# 01_POWER.net
KiCad netlist of a schematic drawn in Altium Designer
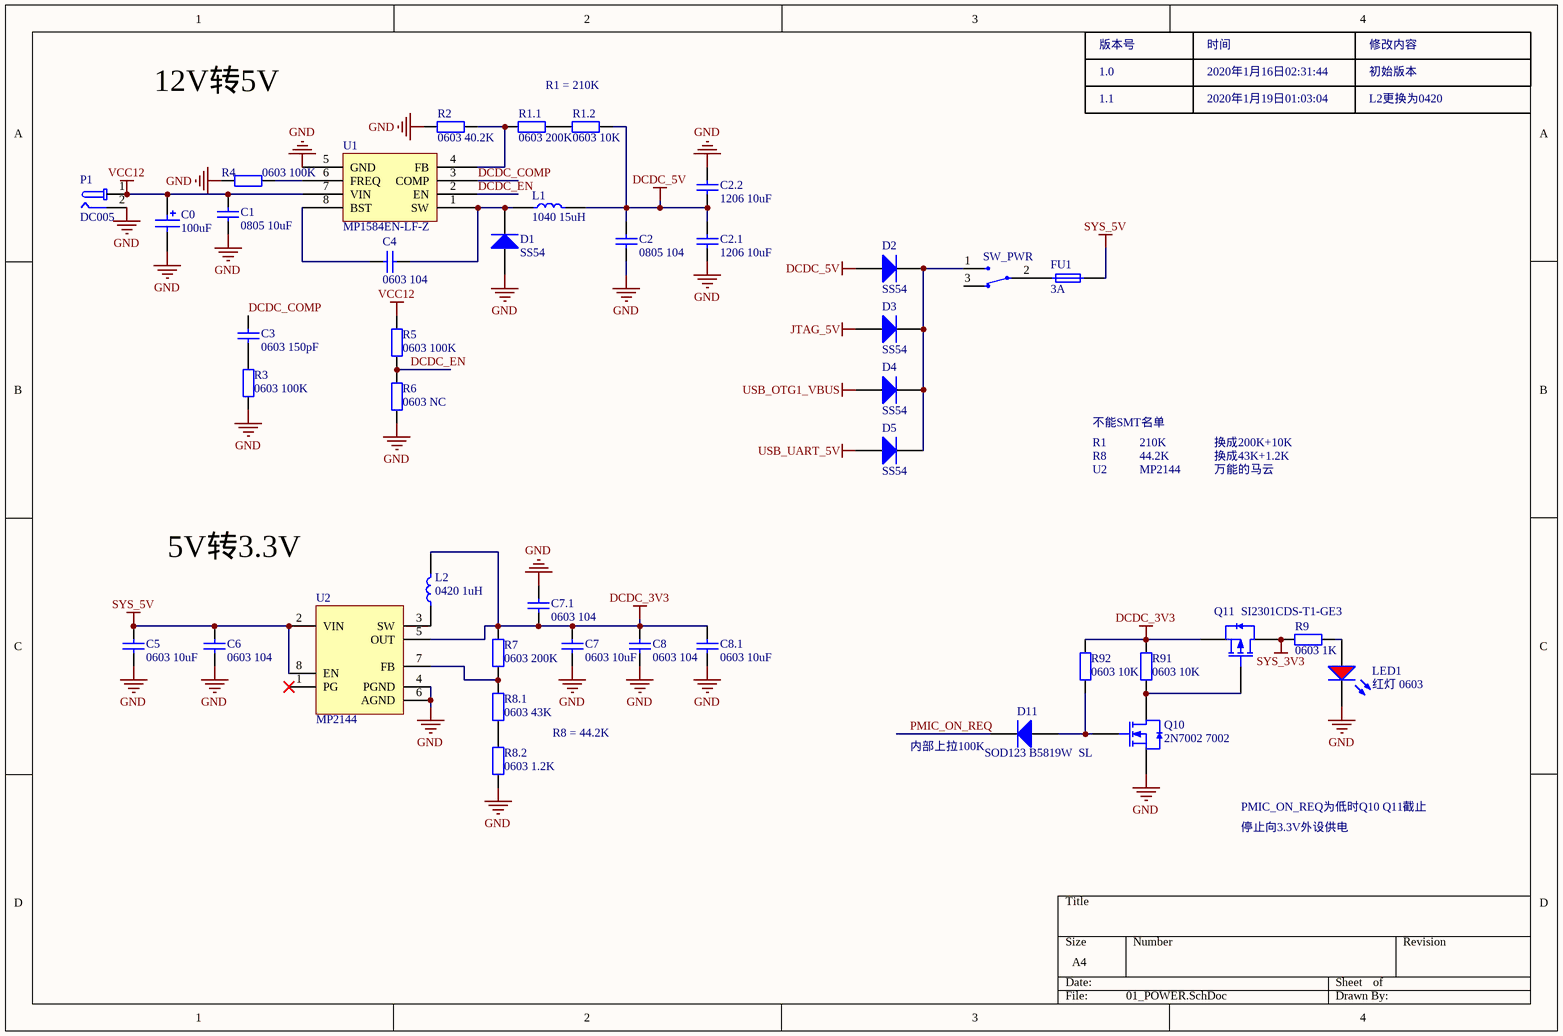
[diagram p0: 01_POWER.SchDoc]

(export (version "E")
  (design (tool "Eeschema 10.0.6"))
  (components
    (comp (ref "C0") (value "100uF") (footprint "CAP1") (libsource (lib "Integrated_Library2") (part "CAP1")))
    (comp (ref "C1")
      (value "0805 10uF")
      (footprint "LC-0805_C")
      (description "贴片电容")
      (libsource (lib "JLC") (part "0805 10uF (106) 10% 25V"))
    )
    (comp (ref "C2")
      (value "0805 104")
      (footprint "LC-0805_C")
      (description "贴片电容")
      (libsource (lib "JLC") (part "0805 10uF (106) 10% 25V"))
    )
    (comp (ref "C2.1")
      (value "1206 10uF")
      (footprint "LC-1206_C")
      (description "贴片电容")
      (libsource (lib "JLC") (part "1206 10uF (106) 10% 50V"))
    )
    (comp (ref "C2.2")
      (value "1206 10uF")
      (footprint "LC-1206_C")
      (description "贴片电容")
      (libsource (lib "JLC") (part "1206 10uF (106) 10% 50V"))
    )
    (comp (ref "C3")
      (value "0603 150pF")
      (footprint "LC-0603_C")
      (description "贴片电容")
      (libsource (lib "JLC") (part "0603 1uF (105) 10% 50V"))
    )
    (comp (ref "C4")
      (value "0603 104")
      (footprint "LC-0603_C")
      (description "贴片电容")
      (libsource (lib "JLC") (part "0603 1uF (105) 10% 50V"))
    )
    (comp (ref "C5")
      (value "0603 10uF")
      (footprint "LC-0603_C")
      (description "贴片电容")
      (libsource (lib "JLC") (part "0603 1uF (105) 10% 50V"))
    )
    (comp (ref "C6")
      (value "0603 104")
      (footprint "LC-0603_C")
      (description "贴片电容")
      (libsource (lib "JLC") (part "0603 1uF (105) 10% 50V"))
    )
    (comp (ref "C7")
      (value "0603 10uF")
      (footprint "LC-0603_C")
      (description "贴片电容")
      (libsource (lib "JLC") (part "0603 1uF (105) 10% 50V"))
    )
    (comp (ref "C7.1")
      (value "0603 104")
      (footprint "LC-0603_C")
      (description "贴片电容")
      (libsource (lib "JLC") (part "0603 1uF (105) 10% 50V"))
    )
    (comp (ref "C8")
      (value "0603 104")
      (footprint "LC-0603_C")
      (description "贴片电容")
      (libsource (lib "JLC") (part "0603 1uF (105) 10% 50V"))
    )
    (comp (ref "C8.1")
      (value "0603 10uF")
      (footprint "LC-0603_C")
      (description "贴片电容")
      (libsource (lib "JLC") (part "0603 1uF (105) 10% 50V"))
    )
    (comp (ref "D1")
      (value "SS54")
      (footprint "LC-SMA(DO-214AC)_S1")
      (description "二极管")
      (libsource (lib "JLC") (part "SMA(DO-214AC) SS54"))
    )
    (comp (ref "D2")
      (value "SS54")
      (footprint "LC-SMA(DO-214AC)_S1")
      (description "二极管")
      (libsource (lib "JLC") (part "SMA(DO-214AC) SS54"))
    )
    (comp (ref "D3")
      (value "SS54")
      (footprint "LC-SMA(DO-214AC)_S1")
      (description "二极管")
      (libsource (lib "JLC") (part "SMA(DO-214AC) SS54"))
    )
    (comp (ref "D4")
      (value "SS54")
      (footprint "LC-SMA(DO-214AC)_S1")
      (description "二极管")
      (libsource (lib "JLC") (part "SMA(DO-214AC) SS54"))
    )
    (comp (ref "D5")
      (value "SS54")
      (footprint "LC-SMA(DO-214AC)_S1")
      (description "二极管")
      (libsource (lib "JLC") (part "SMA(DO-214AC) SS54"))
    )
    (comp (ref "D11")
      (value "SOD123 B5819W  SL")
      (footprint "LC-SOD-123")
      (description "肖特基二极管")
      (libsource (lib "JLC") (part "SOD-123 B5819W  SL"))
    )
    (comp (ref "FU1")
      (value "3A")
      (footprint "1812_FUSOR")
      (libsource (lib "Integrated_Library2") (part "FU"))
    )
    (comp (ref "L1")
      (value "1040 15uH")
      (footprint "L_1040")
      (libsource (lib "Integrated_Library2") (part "Inductor"))
    )
    (comp (ref "L2")
      (value "0420 1uH")
      (footprint "L_0420")
      (libsource (lib "Integrated_Library2") (part "Inductor"))
    )
    (comp (ref "LED1")
      (value "红灯 0603")
      (footprint "LC-0603_LED_S1")
      (description "发光二极管")
      (libsource (lib "JLC") (part "0603 红灯"))
    )
    (comp (ref "P1")
      (value "DC005")
      (footprint "DC005")
      (libsource (lib "Integrated_Library2") (part "DC005"))
    )
    (comp (ref "Q10")
      (value "2N7002 7002")
      (footprint "LC-SOT-23(SOT-23-3)")
      (description "MOS(场效应管)")
      (libsource (lib "JLC") (part "2N7002 7002"))
    )
    (comp (ref "Q11")
      (value "SI2301CDS-T1-GE3")
      (footprint "LC-SOT-23(SOT-23-3)")
      (description "MOS(场效应管)")
      (libsource (lib "JLC") (part "SI2301CDS-T1-GE3"))
    )
    (comp (ref "R1.1")
      (value "0603 200K")
      (footprint "LC-0603_R")
      (description "贴片电阻")
      (libsource (lib "") (part "0603 2.2KΩ (2201) 1%_1"))
    )
    (comp (ref "R1.2")
      (value "0603 10K")
      (footprint "LC-0603_R")
      (description "贴片电阻")
      (libsource (lib "") (part "0603 2.2KΩ (2201) 1%_1"))
    )
    (comp (ref "R2")
      (value "0603 40.2K")
      (footprint "LC-0603_R")
      (description "贴片电阻")
      (libsource (lib "") (part "0603 2.2KΩ (2201) 1%_1"))
    )
    (comp (ref "R3")
      (value "0603 100K")
      (footprint "LC-0603_R")
      (description "贴片电阻")
      (libsource (lib "JLC") (part "0603 2.2KΩ (2201) 1%"))
    )
    (comp (ref "R4")
      (value "0603 100K")
      (footprint "LC-0603_R")
      (description "贴片电阻")
      (libsource (lib "") (part "0603 2.2KΩ (2201) 1%_1"))
    )
    (comp (ref "R5")
      (value "0603 100K")
      (footprint "LC-0603_R")
      (description "贴片电阻")
      (libsource (lib "JLC") (part "0603 2.2KΩ (2201) 1%"))
    )
    (comp (ref "R6")
      (value "0603 NC")
      (footprint "LC-0603_R")
      (description "贴片电阻")
      (libsource (lib "JLC") (part "0603 2.2KΩ (2201) 1%"))
    )
    (comp (ref "R7")
      (value "0603 200K")
      (footprint "LC-0603_R")
      (description "贴片电阻")
      (libsource (lib "JLC") (part "0603 2.2KΩ (2201) 1%"))
    )
    (comp (ref "R8.1")
      (value "0603 43K")
      (footprint "LC-0603_R")
      (description "贴片电阻")
      (libsource (lib "JLC") (part "0603 2.2KΩ (2201) 1%"))
    )
    (comp (ref "R8.2")
      (value "0603 1.2K")
      (footprint "LC-0603_R")
      (description "贴片电阻")
      (libsource (lib "JLC") (part "0603 2.2KΩ (2201) 1%"))
    )
    (comp (ref "R9")
      (value "0603 1K")
      (footprint "LC-0603_R")
      (description "贴片电阻")
      (libsource (lib "") (part "0603 2.2KΩ (2201) 1%_2"))
    )
    (comp (ref "R91")
      (value "0603 10K")
      (footprint "LC-0603_R")
      (description "贴片电阻")
      (libsource (lib "JLC") (part "0603 1.1KΩ (1101) 1%"))
    )
    (comp (ref "R92")
      (value "0603 10K")
      (footprint "LC-0603_R")
      (description "贴片电阻")
      (libsource (lib "JLC") (part "0603 1.1KΩ (1101) 1%"))
    )
    (comp (ref "SW_PWR")
      (value "~")
      (footprint "SW_3P1")
      (libsource (lib "Integrated_Library2") (part "SW_3P"))
    )
    (comp (ref "U1")
      (value "MP1584EN-LF-Z")
      (footprint "LC-SOIC-8_EP_150mil")
      (description "DC-DC芯片")
      (libsource (lib "JLC") (part "MP1584EN-LF-Z"))
    )
    (comp (ref "U2")
      (value "MP2144")
      (footprint "SOT23-8L")
      (libsource (lib "IMX6ULL_CORE(核心板)_V1.4") (part "MP2144"))
    )
  )
  (nets
    (net (code "1") (name "/DCDC_COMP") (class "Default")
      (node (ref "C3") (pin "2") (pinfunction "2_2") (pintype "passive"))
      (node (ref "U1") (pin "3") (pinfunction "COMP_3") (pintype "passive"))
    )
    (net (code "2") (name "/DCDC_EN") (class "Default")
      (node (ref "R5") (pin "1") (pinfunction "1_1") (pintype "passive"))
      (node (ref "R6") (pin "2") (pinfunction "2_2") (pintype "passive"))
      (node (ref "U1") (pin "2") (pinfunction "EN_2") (pintype "passive"))
    )
    (net (code "3") (name "/PMIC_ON_REQ") (class "Default")
      (node (ref "D11") (pin "2") (pinfunction "K_2") (pintype "passive"))
    )
    (net (code "4") (name "DCDC_3V3") (class "Default")
      (node (ref "C7") (pin "2") (pinfunction "2_2") (pintype "passive"))
      (node (ref "C7.1") (pin "2") (pinfunction "2_2") (pintype "passive"))
      (node (ref "C8") (pin "2") (pinfunction "2_2") (pintype "passive"))
      (node (ref "C8.1") (pin "2") (pinfunction "2_2") (pintype "passive"))
      (node (ref "L2") (pin "1") (pinfunction "1_1") (pintype "passive"))
      (node (ref "Q11") (pin "2") (pinfunction "S_2") (pintype "passive"))
      (node (ref "R7") (pin "2") (pinfunction "2_2") (pintype "passive"))
      (node (ref "R91") (pin "2") (pinfunction "2_2") (pintype "passive"))
      (node (ref "R92") (pin "2") (pinfunction "2_2") (pintype "passive"))
      (node (ref "U2") (pin "5") (pinfunction "OUT_5") (pintype "passive"))
    )
    (net (code "5") (name "DCDC_5V") (class "Default")
      (node (ref "C2") (pin "2") (pinfunction "2_2") (pintype "passive"))
      (node (ref "C2.1") (pin "2") (pinfunction "2_2") (pintype "passive"))
      (node (ref "C2.2") (pin "2") (pinfunction "2_2") (pintype "passive"))
      (node (ref "D2") (pin "1") (pinfunction "A_1") (pintype "passive"))
      (node (ref "L1") (pin "1") (pinfunction "1_1") (pintype "passive"))
      (node (ref "R1.2") (pin "2") (pinfunction "2_2") (pintype "passive"))
    )
    (net (code "6") (name "GND") (class "Default")
      (node (ref "C0") (pin "2") (pinfunction "2_2") (pintype "passive"))
      (node (ref "C1") (pin "1") (pinfunction "1_1") (pintype "passive"))
      (node (ref "C2") (pin "1") (pinfunction "1_1") (pintype "passive"))
      (node (ref "C2.1") (pin "1") (pinfunction "1_1") (pintype "passive"))
      (node (ref "C2.2") (pin "1") (pinfunction "1_1") (pintype "passive"))
      (node (ref "C5") (pin "1") (pinfunction "1_1") (pintype "passive"))
      (node (ref "C6") (pin "1") (pinfunction "1_1") (pintype "passive"))
      (node (ref "C7") (pin "1") (pinfunction "1_1") (pintype "passive"))
      (node (ref "C7.1") (pin "1") (pinfunction "1_1") (pintype "passive"))
      (node (ref "C8") (pin "1") (pinfunction "1_1") (pintype "passive"))
      (node (ref "C8.1") (pin "1") (pinfunction "1_1") (pintype "passive"))
      (node (ref "D1") (pin "1") (pinfunction "A_1") (pintype "passive"))
      (node (ref "LED1") (pin "K") (pinfunction "K_K") (pintype "passive"))
      (node (ref "P1") (pin "2") (pinfunction "2_2") (pintype "passive"))
      (node (ref "Q10") (pin "2") (pinfunction "S_2") (pintype "passive"))
      (node (ref "R2") (pin "1") (pinfunction "1_1") (pintype "passive"))
      (node (ref "R3") (pin "1") (pinfunction "1_1") (pintype "passive"))
      (node (ref "R4") (pin "1") (pinfunction "1_1") (pintype "passive"))
      (node (ref "R6") (pin "1") (pinfunction "1_1") (pintype "passive"))
      (node (ref "R8.2") (pin "1") (pinfunction "1_1") (pintype "passive"))
      (node (ref "U1") (pin "5") (pinfunction "GND_5") (pintype "passive"))
      (node (ref "U2") (pin "4") (pinfunction "PGND_4") (pintype "passive"))
      (node (ref "U2") (pin "6") (pinfunction "AGND_6") (pintype "passive"))
    )
    (net (code "7") (name "JTAG_5V") (class "Default")
      (node (ref "D3") (pin "1") (pinfunction "A_1") (pintype "passive"))
    )
    (net (code "8") (name "Net-(C3-Pad1)") (class "Default")
      (node (ref "C3") (pin "1") (pinfunction "1_1") (pintype "passive"))
      (node (ref "R3") (pin "2") (pinfunction "2_2") (pintype "passive"))
    )
    (net (code "9") (name "Net-(D1-K)") (class "Default")
      (node (ref "C4") (pin "2") (pinfunction "2_2") (pintype "passive"))
      (node (ref "D1") (pin "2") (pinfunction "K_2") (pintype "passive"))
      (node (ref "L1") (pin "2") (pinfunction "2_2") (pintype "passive"))
      (node (ref "U1") (pin "1") (pinfunction "SW_1") (pintype "passive"))
    )
    (net (code "10") (name "Net-(D2-K)") (class "Default")
      (node (ref "D2") (pin "2") (pinfunction "K_2") (pintype "passive"))
      (node (ref "D3") (pin "2") (pinfunction "K_2") (pintype "passive"))
      (node (ref "D4") (pin "2") (pinfunction "K_2") (pintype "passive"))
      (node (ref "D5") (pin "2") (pinfunction "K_2") (pintype "passive"))
      (node (ref "SW_PWR") (pin "1") (pinfunction "1_1") (pintype "passive"))
    )
    (net (code "11") (name "Net-(D11-A)") (class "Default")
      (node (ref "D11") (pin "1") (pinfunction "A_1") (pintype "passive"))
      (node (ref "Q10") (pin "1") (pinfunction "G_1") (pintype "passive"))
      (node (ref "R92") (pin "1") (pinfunction "1_1") (pintype "passive"))
    )
    (net (code "12") (name "Net-(FU1-Pad1)") (class "Default")
      (node (ref "FU1") (pin "1") (pinfunction "1_1") (pintype "passive"))
      (node (ref "SW_PWR") (pin "2") (pinfunction "2_2") (pintype "passive"))
    )
    (net (code "13") (name "Net-(LED1-PadA)") (class "Default")
      (node (ref "LED1") (pin "A") (pinfunction "A_A") (pintype "passive"))
      (node (ref "R9") (pin "1") (pinfunction "1_1") (pintype "passive"))
    )
    (net (code "14") (name "Net-(Q10-D)") (class "Default")
      (node (ref "Q10") (pin "3") (pinfunction "D_3") (pintype "passive"))
      (node (ref "Q11") (pin "1") (pinfunction "G_1") (pintype "passive"))
      (node (ref "R91") (pin "1") (pinfunction "1_1") (pintype "passive"))
    )
    (net (code "15") (name "Net-(R1.1-Pad2)") (class "Default")
      (node (ref "R1.1") (pin "2") (pinfunction "2_2") (pintype "passive"))
      (node (ref "R1.2") (pin "1") (pinfunction "1_1") (pintype "passive"))
    )
    (net (code "16") (name "Net-(R8.1-Pad1)") (class "Default")
      (node (ref "R8.1") (pin "1") (pinfunction "1_1") (pintype "passive"))
      (node (ref "R8.2") (pin "2") (pinfunction "2_2") (pintype "passive"))
    )
    (net (code "17") (name "Net-(U1-BST)") (class "Default")
      (node (ref "C4") (pin "1") (pinfunction "1_1") (pintype "passive"))
      (node (ref "U1") (pin "8") (pinfunction "BST_8") (pintype "passive"))
    )
    (net (code "18") (name "Net-(U1-FB)") (class "Default")
      (node (ref "R1.1") (pin "1") (pinfunction "1_1") (pintype "passive"))
      (node (ref "R2") (pin "2") (pinfunction "2_2") (pintype "passive"))
      (node (ref "U1") (pin "4") (pinfunction "FB_4") (pintype "passive"))
    )
    (net (code "19") (name "Net-(U1-FREQ)") (class "Default")
      (node (ref "R4") (pin "2") (pinfunction "2_2") (pintype "passive"))
      (node (ref "U1") (pin "6") (pinfunction "FREQ_6") (pintype "passive"))
    )
    (net (code "20") (name "Net-(U2-FB)") (class "Default")
      (node (ref "R7") (pin "1") (pinfunction "1_1") (pintype "passive"))
      (node (ref "R8.1") (pin "2") (pinfunction "2_2") (pintype "passive"))
      (node (ref "U2") (pin "7") (pinfunction "FB_7") (pintype "passive"))
    )
    (net (code "21") (name "Net-(U2-SW)") (class "Default")
      (node (ref "L2") (pin "2") (pinfunction "2_2") (pintype "passive"))
      (node (ref "U2") (pin "3") (pinfunction "SW_3") (pintype "passive"))
    )
    (net (code "22") (name "SYS_3V3") (class "Default")
      (node (ref "Q11") (pin "3") (pinfunction "D_3") (pintype "passive"))
      (node (ref "R9") (pin "2") (pinfunction "2_2") (pintype "passive"))
    )
    (net (code "23") (name "SYS_5V") (class "Default")
      (node (ref "C5") (pin "2") (pinfunction "2_2") (pintype "passive"))
      (node (ref "C6") (pin "2") (pinfunction "2_2") (pintype "passive"))
      (node (ref "FU1") (pin "2") (pinfunction "2_2") (pintype "passive"))
      (node (ref "U2") (pin "2") (pinfunction "VIN_2") (pintype "passive"))
      (node (ref "U2") (pin "8") (pinfunction "EN_8") (pintype "passive"))
    )
    (net (code "24") (name "USB_OTG1_VBUS") (class "Default")
      (node (ref "D4") (pin "1") (pinfunction "A_1") (pintype "passive"))
    )
    (net (code "25") (name "USB_UART_5V") (class "Default")
      (node (ref "D5") (pin "1") (pinfunction "A_1") (pintype "passive"))
    )
    (net (code "26") (name "VCC12") (class "Default")
      (node (ref "C0") (pin "1") (pinfunction "1_1") (pintype "passive"))
      (node (ref "C1") (pin "2") (pinfunction "2_2") (pintype "passive"))
      (node (ref "P1") (pin "1") (pinfunction "1_1") (pintype "passive"))
      (node (ref "R5") (pin "2") (pinfunction "2_2") (pintype "passive"))
      (node (ref "U1") (pin "7") (pinfunction "VIN_7") (pintype "passive"))
    )
    (net (code "27") (name "unconnected-(SW_PWR-Pad3)") (class "Default")
      (node (ref "SW_PWR") (pin "3") (pinfunction "3_3") (pintype "passive"))
    )
    (net (code "28") (name "unconnected-(U2-PG-Pad1)") (class "Default")
      (node (ref "U2") (pin "1") (pinfunction "PG_1") (pintype "passive+no_connect"))
    )
  )
)
